# SHEET1.net
KiCad netlist of a schematic drawn in Altium Designer
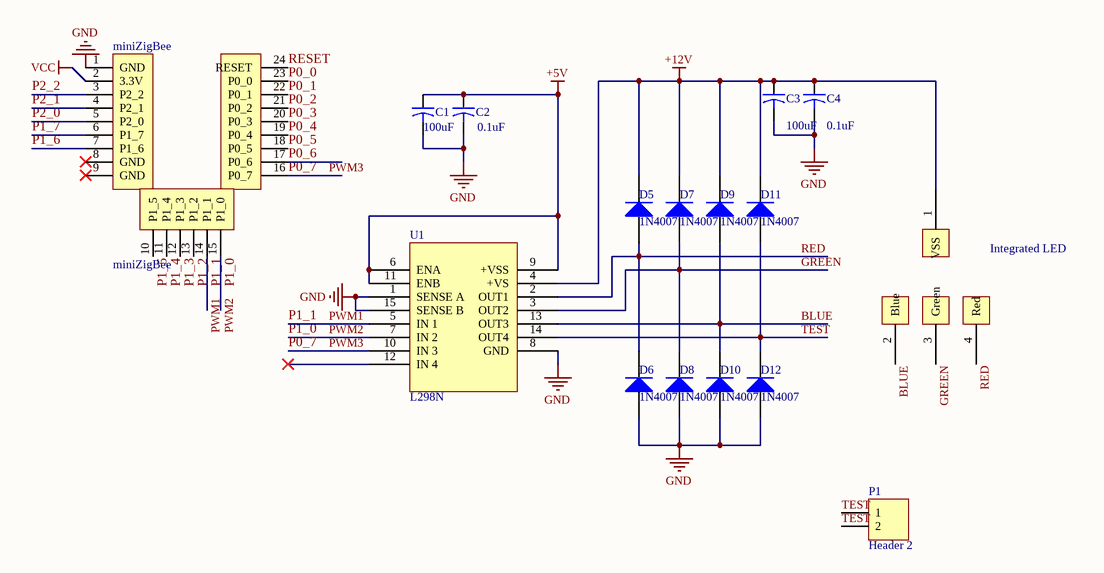
[diagram p0: SHEET1.SCHDOC]

(export (version "E")
  (design (tool "Eeschema 10.0.6"))
  (components
    (comp (ref "C1")
      (value "100uF")
      (footprint "CAPR5-4X5")
      (description "Capacitor")
      (fields (field (name "PUBLISHER") "Altium Limited"))
      (libsource (lib "Miscellaneous Devices") (part "Cap2"))
    )
    (comp (ref "C2")
      (value "0.1uF")
      (footprint "CAPR5-4X5")
      (description "Capacitor")
      (fields (field (name "PUBLISHER") "Altium Limited"))
      (libsource (lib "Miscellaneous Devices") (part "Cap2"))
    )
    (comp (ref "C3")
      (value "100uF")
      (footprint "CAPR5-4X5")
      (description "Capacitor")
      (fields (field (name "PUBLISHER") "Altium Limited"))
      (libsource (lib "Miscellaneous Devices") (part "Cap2"))
    )
    (comp (ref "C4")
      (value "0.1uF")
      (footprint "CAPR5-4X5")
      (description "Capacitor")
      (fields (field (name "PUBLISHER") "Altium Limited"))
      (libsource (lib "Miscellaneous Devices") (part "Cap2"))
    )
    (comp (ref "D5")
      (value "1N4007")
      (footprint "DO-41")
      (description "1 Amp General Purpose Rectifier")
      (fields (field (name "PUBLISHER") "Altium Limited"))
      (libsource (lib "Miscellaneous Devices") (part "Diode 1N4007"))
    )
    (comp (ref "D6")
      (value "1N4007")
      (footprint "DO-41")
      (description "1 Amp General Purpose Rectifier")
      (fields (field (name "PUBLISHER") "Altium Limited"))
      (libsource (lib "Miscellaneous Devices") (part "Diode 1N4007"))
    )
    (comp (ref "D7")
      (value "1N4007")
      (footprint "DO-41")
      (description "1 Amp General Purpose Rectifier")
      (fields (field (name "PUBLISHER") "Altium Limited"))
      (libsource (lib "Miscellaneous Devices") (part "Diode 1N4007"))
    )
    (comp (ref "D8")
      (value "1N4007")
      (footprint "DO-41")
      (description "1 Amp General Purpose Rectifier")
      (fields (field (name "PUBLISHER") "Altium Limited"))
      (libsource (lib "Miscellaneous Devices") (part "Diode 1N4007"))
    )
    (comp (ref "D9")
      (value "1N4007")
      (footprint "DO-41")
      (description "1 Amp General Purpose Rectifier")
      (fields (field (name "PUBLISHER") "Altium Limited"))
      (libsource (lib "Miscellaneous Devices") (part "Diode 1N4007"))
    )
    (comp (ref "D10")
      (value "1N4007")
      (footprint "DO-41")
      (description "1 Amp General Purpose Rectifier")
      (fields (field (name "PUBLISHER") "Altium Limited"))
      (libsource (lib "Miscellaneous Devices") (part "Diode 1N4007"))
    )
    (comp (ref "D11")
      (value "1N4007")
      (footprint "DO-41")
      (description "1 Amp General Purpose Rectifier")
      (fields (field (name "PUBLISHER") "Altium Limited"))
      (libsource (lib "Miscellaneous Devices") (part "Diode 1N4007"))
    )
    (comp (ref "D12")
      (value "1N4007")
      (footprint "DO-41")
      (description "1 Amp General Purpose Rectifier")
      (fields (field (name "PUBLISHER") "Altium Limited"))
      (libsource (lib "Miscellaneous Devices") (part "Diode 1N4007"))
    )
    (comp (ref "Integrated LED")
      (value "Integrated LED")
      (footprint "Integrated LED")
      (libsource (lib "my Integrated lib ") (part "Integrated LED"))
    )
    (comp (ref "miniZigBee")
      (value "miniZigBee")
      (footprint "miniZigBee")
      (libsource (lib "my Integrated lib ") (part "miniZigBee"))
    )
    (comp (ref "P1")
      (value "Header 2")
      (footprint "HDR1X2")
      (description "Header, 2-Pin")
      (fields (field (name "PUBLISHER") "Altium Limited"))
      (libsource (lib "Miscellaneous Connectors") (part "Header 2"))
    )
    (comp (ref "U1") (value "L298N") (footprint "L298N - duplicate") (libsource (lib "KU1") (part "L298N")))
  )
  (nets
    (net (code "1") (name "+5V") (class "Default")
      (node (ref "C1") (pin "1") (pinfunction "1_1") (pintype "passive"))
      (node (ref "C2") (pin "1") (pinfunction "1_1") (pintype "passive"))
      (node (ref "U1") (pin "11") (pinfunction "ENB_11") (pintype "passive"))
      (node (ref "U1") (pin "6") (pinfunction "ENA_6") (pintype "passive"))
      (node (ref "U1") (pin "9") (pinfunction "+VSS_9") (pintype "passive"))
    )
    (net (code "2") (name "+12V") (class "Default")
      (node (ref "C3") (pin "1") (pinfunction "1_1") (pintype "passive"))
      (node (ref "C4") (pin "1") (pinfunction "1_1") (pintype "passive"))
      (node (ref "D11") (pin "2") (pinfunction "K_2") (pintype "passive"))
      (node (ref "D5") (pin "2") (pinfunction "K_2") (pintype "passive"))
      (node (ref "D7") (pin "2") (pinfunction "K_2") (pintype "passive"))
      (node (ref "D9") (pin "2") (pinfunction "K_2") (pintype "passive"))
      (node (ref "Integrated LED") (pin "1") (pinfunction "VSS_1") (pintype "passive"))
      (node (ref "U1") (pin "4") (pinfunction "+VS_4") (pintype "passive"))
    )
    (net (code "3") (name "/BLUE") (class "Default")
      (node (ref "D10") (pin "2") (pinfunction "K_2") (pintype "passive"))
      (node (ref "D9") (pin "1") (pinfunction "A_1") (pintype "passive"))
      (node (ref "Integrated LED") (pin "2") (pinfunction "Blue_2") (pintype "passive"))
      (node (ref "U1") (pin "13") (pinfunction "OUT3_13") (pintype "passive"))
    )
    (net (code "4") (name "/GREEN") (class "Default")
      (node (ref "D7") (pin "1") (pinfunction "A_1") (pintype "passive"))
      (node (ref "D8") (pin "2") (pinfunction "K_2") (pintype "passive"))
      (node (ref "Integrated LED") (pin "3") (pinfunction "Green_3") (pintype "passive"))
      (node (ref "U1") (pin "3") (pinfunction "OUT2_3") (pintype "passive"))
    )
    (net (code "5") (name "/P0_0") (class "Default")
      (node (ref "miniZigBee") (pin "23") (pinfunction "P0_0_23") (pintype "passive"))
    )
    (net (code "6") (name "/P0_1") (class "Default")
      (node (ref "miniZigBee") (pin "22") (pinfunction "P0_1_22") (pintype "passive"))
    )
    (net (code "7") (name "/P0_2") (class "Default")
      (node (ref "miniZigBee") (pin "21") (pinfunction "P0_2_21") (pintype "passive"))
    )
    (net (code "8") (name "/P0_3") (class "Default")
      (node (ref "miniZigBee") (pin "20") (pinfunction "P0_3_20") (pintype "passive"))
    )
    (net (code "9") (name "/P0_4") (class "Default")
      (node (ref "miniZigBee") (pin "19") (pinfunction "P0_4_19") (pintype "passive"))
    )
    (net (code "10") (name "/P0_5") (class "Default")
      (node (ref "miniZigBee") (pin "18") (pinfunction "P0_5_18") (pintype "passive"))
    )
    (net (code "11") (name "/P0_6") (class "Default")
      (node (ref "miniZigBee") (pin "17") (pinfunction "P0_6_17") (pintype "passive"))
    )
    (net (code "12") (name "/P0_7") (class "Default")
      (node (ref "U1") (pin "10") (pinfunction "IN_3_10") (pintype "passive"))
      (node (ref "miniZigBee") (pin "16") (pinfunction "P0_7_16") (pintype "passive"))
    )
    (net (code "13") (name "/P1_0") (class "Default")
      (node (ref "U1") (pin "7") (pinfunction "IN_2_7") (pintype "passive"))
      (node (ref "miniZigBee") (pin "15") (pinfunction "P1_0_15") (pintype "passive"))
    )
    (net (code "14") (name "/P1_1") (class "Default")
      (node (ref "U1") (pin "5") (pinfunction "IN_1_5") (pintype "passive"))
      (node (ref "miniZigBee") (pin "14") (pinfunction "P1_1_14") (pintype "passive"))
    )
    (net (code "15") (name "/P1_2") (class "Default")
      (node (ref "miniZigBee") (pin "13") (pinfunction "P1_2_13") (pintype "passive"))
    )
    (net (code "16") (name "/P1_3") (class "Default")
      (node (ref "miniZigBee") (pin "12") (pinfunction "P1_3_12") (pintype "passive"))
    )
    (net (code "17") (name "/P1_4") (class "Default")
      (node (ref "miniZigBee") (pin "11") (pinfunction "P1_4_11") (pintype "passive"))
    )
    (net (code "18") (name "/P1_5") (class "Default")
      (node (ref "miniZigBee") (pin "10") (pinfunction "P1_5_10") (pintype "passive"))
    )
    (net (code "19") (name "/P1_6") (class "Default")
      (node (ref "miniZigBee") (pin "7") (pinfunction "P1_6_7") (pintype "passive"))
    )
    (net (code "20") (name "/P1_7") (class "Default")
      (node (ref "miniZigBee") (pin "6") (pinfunction "P1_7_6") (pintype "passive"))
    )
    (net (code "21") (name "/P2_0") (class "Default")
      (node (ref "miniZigBee") (pin "5") (pinfunction "P2_0_5") (pintype "passive"))
    )
    (net (code "22") (name "/P2_1") (class "Default")
      (node (ref "miniZigBee") (pin "4") (pinfunction "P2_1_4") (pintype "passive"))
    )
    (net (code "23") (name "/P2_2") (class "Default")
      (node (ref "miniZigBee") (pin "3") (pinfunction "P2_2_3") (pintype "passive"))
    )
    (net (code "24") (name "/RED") (class "Default")
      (node (ref "D5") (pin "1") (pinfunction "A_1") (pintype "passive"))
      (node (ref "D6") (pin "2") (pinfunction "K_2") (pintype "passive"))
      (node (ref "Integrated LED") (pin "4") (pinfunction "Red_4") (pintype "passive"))
      (node (ref "U1") (pin "2") (pinfunction "OUT1_2") (pintype "passive"))
    )
    (net (code "25") (name "/RESET") (class "Default")
      (node (ref "miniZigBee") (pin "24") (pinfunction "RESET_24") (pintype "passive"))
    )
    (net (code "26") (name "/TEST") (class "Default")
      (node (ref "D11") (pin "1") (pinfunction "A_1") (pintype "passive"))
      (node (ref "D12") (pin "2") (pinfunction "K_2") (pintype "passive"))
      (node (ref "P1") (pin "1") (pinfunction "1_1") (pintype "passive"))
      (node (ref "P1") (pin "2") (pinfunction "2_2") (pintype "passive"))
      (node (ref "U1") (pin "14") (pinfunction "OUT4_14") (pintype "passive"))
    )
    (net (code "27") (name "GND") (class "Default")
      (node (ref "C1") (pin "2") (pinfunction "2_2") (pintype "passive"))
      (node (ref "C2") (pin "2") (pinfunction "2_2") (pintype "passive"))
      (node (ref "C3") (pin "2") (pinfunction "2_2") (pintype "passive"))
      (node (ref "C4") (pin "2") (pinfunction "2_2") (pintype "passive"))
      (node (ref "D10") (pin "1") (pinfunction "A_1") (pintype "passive"))
      (node (ref "D12") (pin "1") (pinfunction "A_1") (pintype "passive"))
      (node (ref "D6") (pin "1") (pinfunction "A_1") (pintype "passive"))
      (node (ref "D8") (pin "1") (pinfunction "A_1") (pintype "passive"))
      (node (ref "U1") (pin "1") (pinfunction "SENSE_A_1") (pintype "passive"))
      (node (ref "U1") (pin "15") (pinfunction "SENSE_B_15") (pintype "passive"))
      (node (ref "U1") (pin "8") (pinfunction "GND_8") (pintype "passive"))
      (node (ref "miniZigBee") (pin "1") (pinfunction "GND_1") (pintype "passive"))
    )
    (net (code "28") (name "VCC") (class "Default")
      (node (ref "miniZigBee") (pin "2") (pinfunction "3.3V_2") (pintype "passive"))
    )
    (net (code "29") (name "unconnected-(U1-IN_4-Pad12)") (class "Default")
      (node (ref "U1") (pin "12") (pinfunction "IN_4_12") (pintype "passive+no_connect"))
    )
    (net (code "30") (name "unconnected-(miniZigBee-GND-Pad8)") (class "Default")
      (node (ref "miniZigBee") (pin "8") (pinfunction "GND_8") (pintype "passive+no_connect"))
    )
    (net (code "31") (name "unconnected-(miniZigBee-GND-Pad9)") (class "Default")
      (node (ref "miniZigBee") (pin "9") (pinfunction "GND_9") (pintype "passive+no_connect"))
    )
  )
)
